# Booster_PA_OUT_HL.net
KiCad netlist of a schematic drawn in Altium Designer
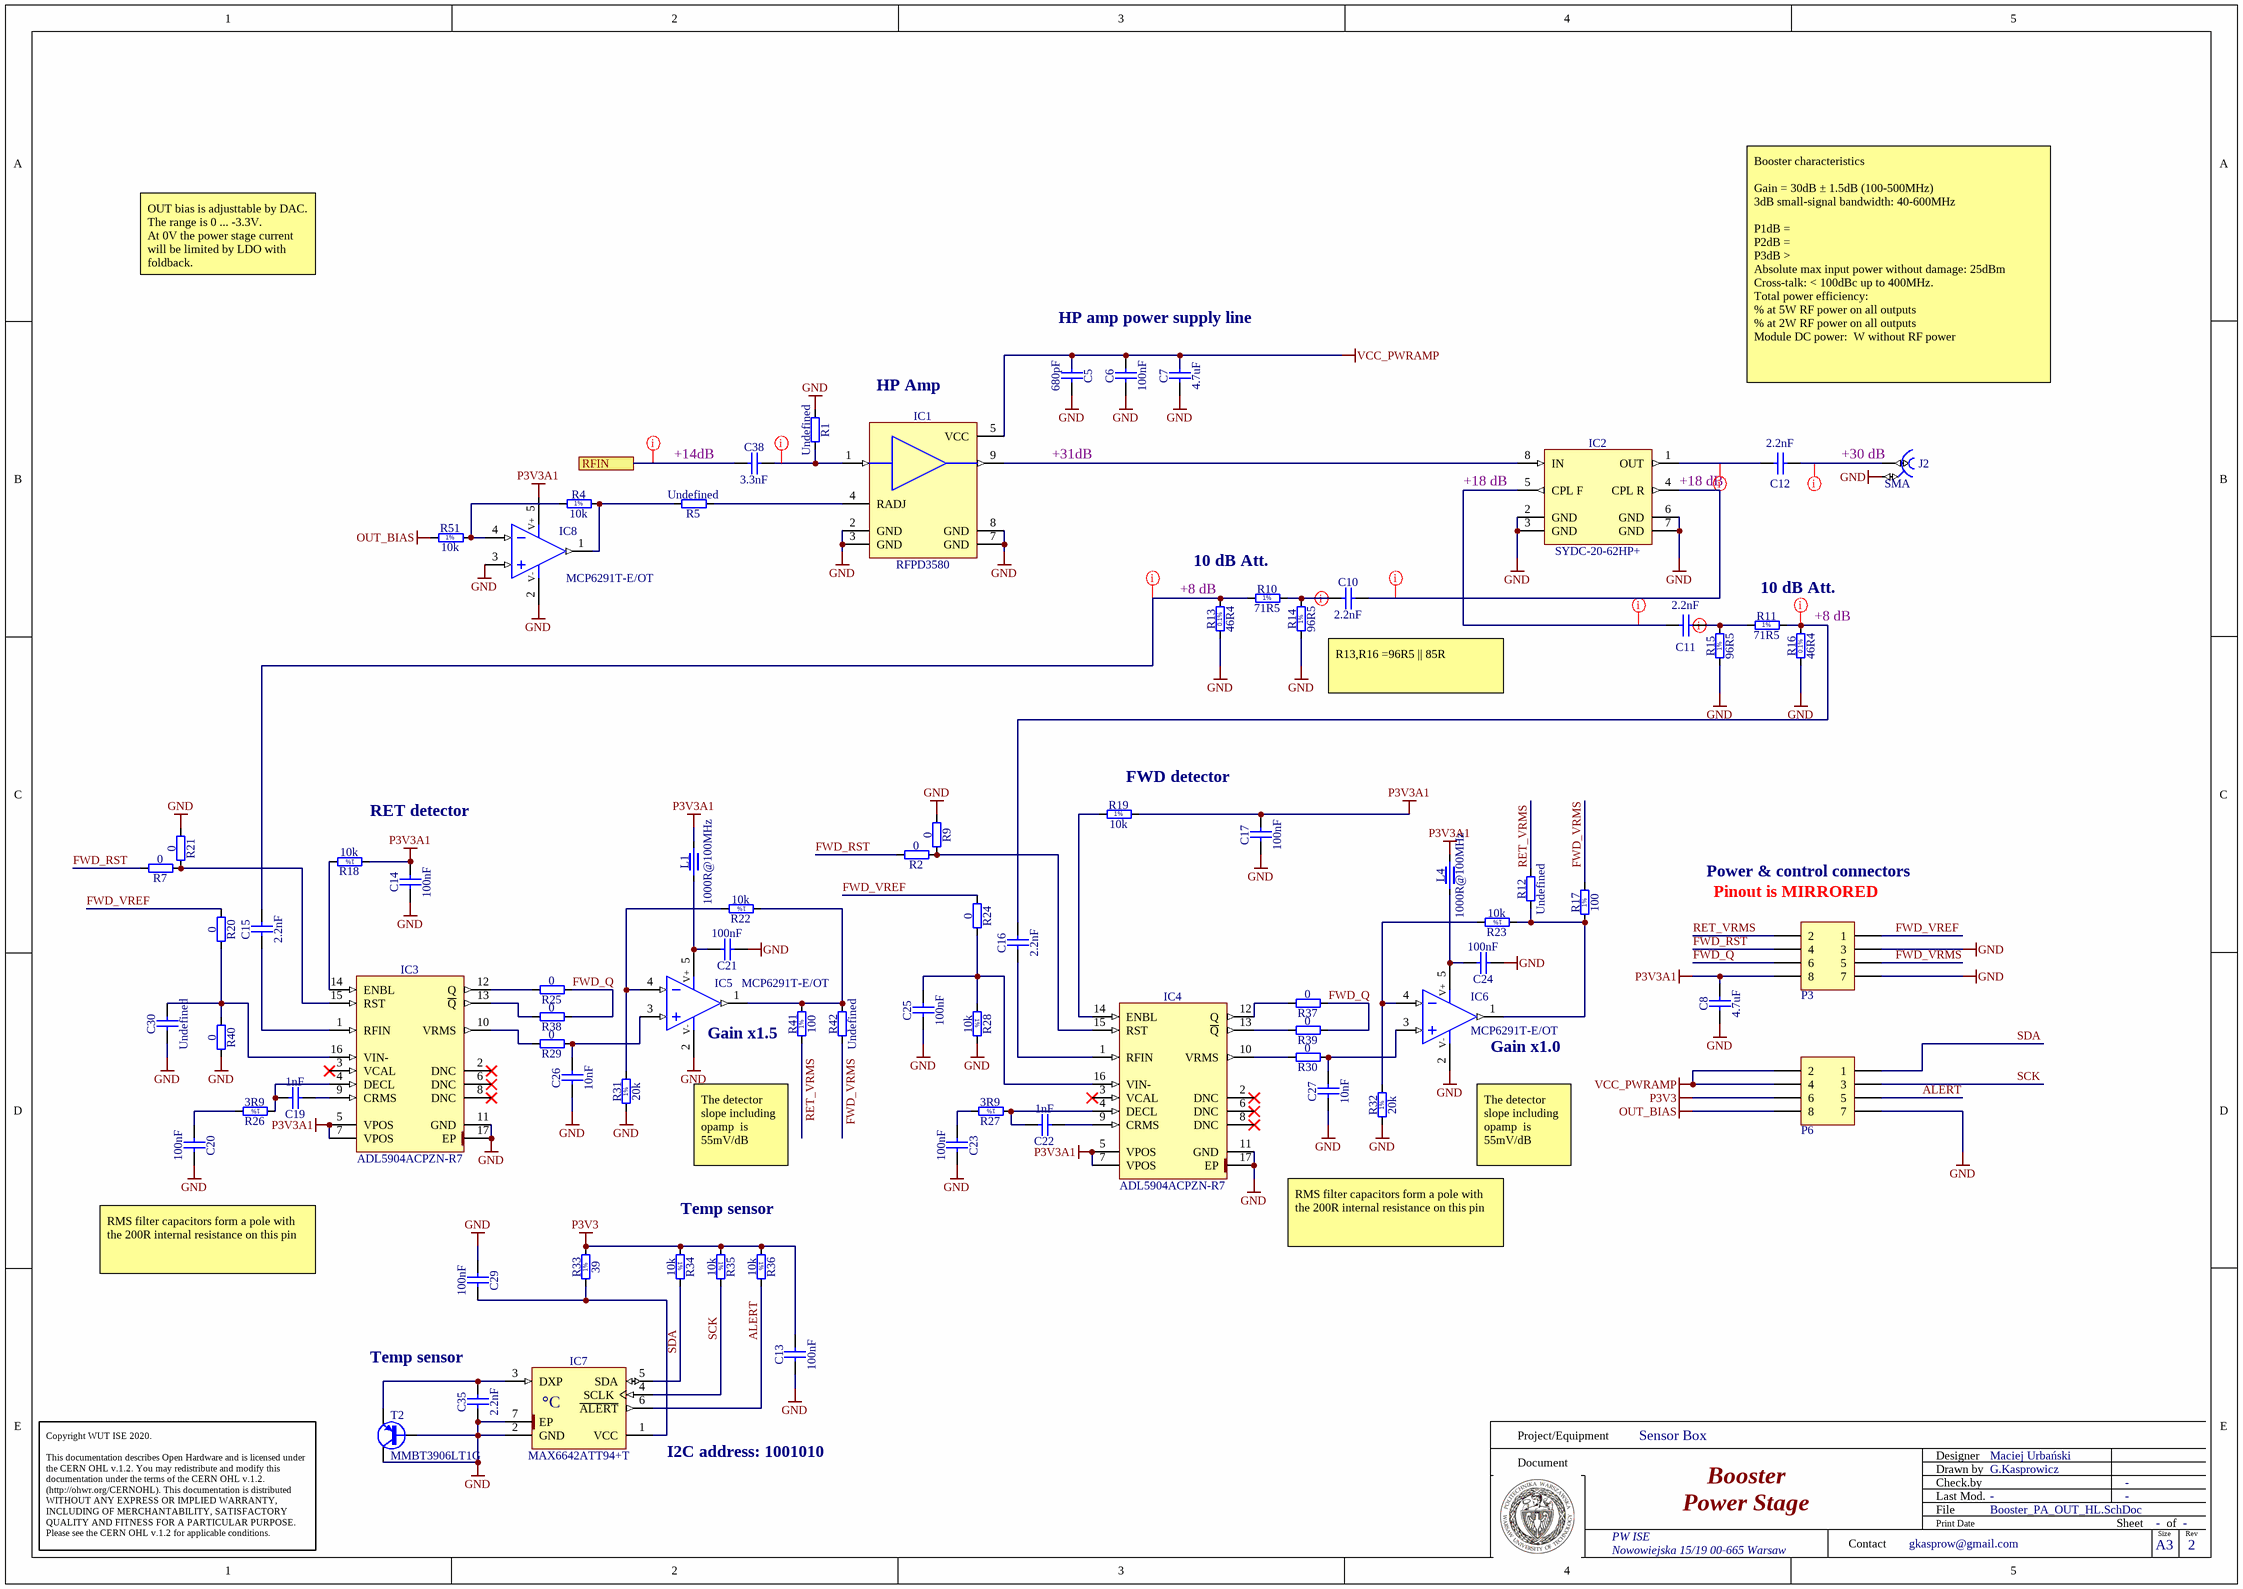
[diagram p0: Booster_PA_OUT_HL.SchDoc]

(export (version "E")
  (design (tool "Eeschema 10.0.6"))
  (components
    (comp (ref "C5")
      (value "680pF")
      (footprint "CAPC1608X87N")
      (description "Non-polarised capacitor")
      (fields
        (field (name "MANUFACTURER") "GENERIC")
        (field (name "MANUFACTURER PART NUMBER") "CC0603_680PF_50V_5%_NP0")
        (field (name "AUTHOR") "CERN DEM JLC")
      )
      (libsource (lib "Capacitors") (part "Capacitor - non polarized"))
    )
    (comp (ref "C6")
      (value "100nF")
      (footprint "CAPC1005X55N")
      (description "Non-polarised capacitor")
      (fields
        (field (name "MANUFACTURER") "GENERIC")
        (field (name "MANUFACTURER PART NUMBER") "CC0402_100NF_50V_10%_X7R")
        (field (name "AUTHOR") "CERN DEM MR")
      )
      (libsource (lib "Capacitors") (part "Capacitor - non polarized"))
    )
    (comp (ref "C7")
      (value "4.7uF")
      (footprint "CAPC3225X270N")
      (description "Non-polarised capacitor")
      (fields
        (field (name "PART NUMBER") "CC1210_4.7UF_50V_10%_X7R")
        (field (name "VOLTAGE") "50V")
        (field (name "AUTHOR") "CERN DEM JLC")
      )
      (libsource (lib "Capacitors") (part "Capacitor - non polarized"))
    )
    (comp (ref "C8")
      (value "4.7uF")
      (footprint "CAPC1709X95N")
      (description "Non-polarised capacitor")
      (fields
        (field (name "MANUFACTURER") "GENERIC")
        (field (name "MANUFACTURER PART NUMBER") "CC0603_4.7UF_16V_10%_X5R")
        (field (name "AUTHOR") "CERN DEM JLC")
      )
      (libsource (lib "Capacitors") (part "Capacitor - non polarized"))
    )
    (comp (ref "C10")
      (value "2.2nF")
      (footprint "CAPC1608X87N")
      (description "Non-polarised capacitor")
      (fields
        (field (name "PART NUMBER") "CC0603_2.2NF_50V_5%_C0G")
        (field (name "VOLTAGE") "50V")
        (field (name "AUTHOR") "CERN DEM JMW")
      )
      (libsource (lib "Capacitors") (part "Capacitor - non polarized"))
    )
    (comp (ref "C11")
      (value "2.2nF")
      (footprint "CAPC1608X87N")
      (description "Non-polarised capacitor")
      (fields
        (field (name "MANUFACTURER") "GENERIC")
        (field (name "MANUFACTURER PART NUMBER") "CC0603_2.2NF_50V_5%_C0G")
        (field (name "AUTHOR") "CERN DEM JMW")
      )
      (libsource (lib "Capacitors") (part "Capacitor - non polarized"))
    )
    (comp (ref "C12")
      (value "2.2nF")
      (footprint "CAPC1608X87N")
      (description "Non-polarised capacitor")
      (fields
        (field (name "MANUFACTURER") "GENERIC")
        (field (name "MANUFACTURER PART NUMBER") "CC0603_2.2NF_50V_5%_C0G")
        (field (name "AUTHOR") "CERN DEM JMW")
      )
      (libsource (lib "Capacitors") (part "Capacitor - non polarized"))
    )
    (comp (ref "C13")
      (value "100nF")
      (footprint "CAPC1005X55N")
      (description "Non-polarised capacitor")
      (fields
        (field (name "MANUFACTURER") "GENERIC")
        (field (name "MANUFACTURER PART NUMBER") "CC0402_100NF_50V_10%_X7R")
        (field (name "AUTHOR") "CERN DEM MR")
      )
      (libsource (lib "Capacitors") (part "Capacitor - non polarized"))
    )
    (comp (ref "C14")
      (value "100nF")
      (footprint "CAPC1005X55N")
      (description "Non-polarised capacitor")
      (fields
        (field (name "MANUFACTURER") "GENERIC")
        (field (name "MANUFACTURER PART NUMBER") "CC0402_100NF_50V_10%_X7R")
        (field (name "AUTHOR") "CERN DEM MR")
      )
      (libsource (lib "Capacitors") (part "Capacitor - non polarized"))
    )
    (comp (ref "C15")
      (value "2.2nF")
      (footprint "CAPC1608X87N")
      (description "Non-polarised capacitor")
      (fields
        (field (name "MANUFACTURER") "GENERIC")
        (field (name "MANUFACTURER PART NUMBER") "CC0603_2.2NF_50V_5%_C0G")
        (field (name "AUTHOR") "CERN DEM JMW")
      )
      (libsource (lib "Capacitors") (part "Capacitor - non polarized"))
    )
    (comp (ref "C16")
      (value "2.2nF")
      (footprint "CAPC1608X87N")
      (description "Non-polarised capacitor")
      (fields
        (field (name "MANUFACTURER") "GENERIC")
        (field (name "MANUFACTURER PART NUMBER") "CC0603_2.2NF_50V_5%_C0G")
        (field (name "AUTHOR") "CERN DEM JMW")
      )
      (libsource (lib "Capacitors") (part "Capacitor - non polarized"))
    )
    (comp (ref "C17")
      (value "100nF")
      (footprint "CAPC1005X55N")
      (description "Non-polarised capacitor")
      (fields
        (field (name "MANUFACTURER") "GENERIC")
        (field (name "MANUFACTURER PART NUMBER") "CC0402_100NF_50V_10%_X7R")
        (field (name "AUTHOR") "CERN DEM MR")
      )
      (libsource (lib "Capacitors") (part "Capacitor - non polarized"))
    )
    (comp (ref "C19")
      (value "1nF")
      (footprint "CAPC1005X55N")
      (description "Non-polarised capacitor")
      (fields
        (field (name "PART NUMBER") "CC0402_1NF_50V_10%_X7R")
        (field (name "VOLTAGE") "50V")
        (field (name "AUTHOR") "CERN DEM JLC")
      )
      (libsource (lib "Capacitors") (part "Capacitor - non polarized"))
    )
    (comp (ref "C20")
      (value "100nF")
      (footprint "CAPC1005X55N")
      (description "Non-polarised capacitor")
      (fields
        (field (name "MANUFACTURER") "GENERIC")
        (field (name "MANUFACTURER PART NUMBER") "CC0402_100NF_50V_10%_X7R")
        (field (name "AUTHOR") "CERN DEM MR")
      )
      (libsource (lib "Capacitors") (part "Capacitor - non polarized"))
    )
    (comp (ref "C21")
      (value "100nF")
      (footprint "CAPC1005X55N")
      (description "Non-polarised capacitor")
      (fields
        (field (name "MANUFACTURER") "GENERIC")
        (field (name "MANUFACTURER PART NUMBER") "CC0402_100NF_50V_10%_X7R")
        (field (name "AUTHOR") "CERN DEM MR")
      )
      (libsource (lib "Capacitors") (part "Capacitor - non polarized"))
    )
    (comp (ref "C22")
      (value "1nF")
      (footprint "CAPC1005X55N")
      (description "Non-polarised capacitor")
      (fields
        (field (name "PART NUMBER") "CC0402_1NF_50V_10%_X7R")
        (field (name "VOLTAGE") "50V")
        (field (name "AUTHOR") "CERN DEM JLC")
      )
      (libsource (lib "Capacitors") (part "Capacitor - non polarized"))
    )
    (comp (ref "C23")
      (value "100nF")
      (footprint "CAPC1005X55N")
      (description "Non-polarised capacitor")
      (fields
        (field (name "MANUFACTURER") "GENERIC")
        (field (name "MANUFACTURER PART NUMBER") "CC0402_100NF_50V_10%_X7R")
        (field (name "AUTHOR") "CERN DEM MR")
      )
      (libsource (lib "Capacitors") (part "Capacitor - non polarized"))
    )
    (comp (ref "C24")
      (value "100nF")
      (footprint "CAPC1005X55N")
      (description "Non-polarised capacitor")
      (fields
        (field (name "MANUFACTURER") "GENERIC")
        (field (name "MANUFACTURER PART NUMBER") "CC0402_100NF_50V_10%_X7R")
        (field (name "AUTHOR") "CERN DEM MR")
      )
      (libsource (lib "Capacitors") (part "Capacitor - non polarized"))
    )
    (comp (ref "C25")
      (value "100nF")
      (footprint "CAPC1005X55N")
      (description "Non-polarised capacitor")
      (fields
        (field (name "MANUFACTURER") "GENERIC")
        (field (name "MANUFACTURER PART NUMBER") "CC0402_100NF_50V_10%_X7R")
        (field (name "AUTHOR") "CERN DEM MR")
      )
      (libsource (lib "Capacitors") (part "Capacitor - non polarized"))
    )
    (comp (ref "C26")
      (value "10nF")
      (footprint "CAPC1005X55N")
      (description "Non-polarised capacitor")
      (fields
        (field (name "MANUFACTURER") "GENERIC")
        (field (name "MANUFACTURER PART NUMBER") "CC0402_10NF_25V_10%_X7R")
        (field (name "AUTHOR") "CERN DEM JLC")
      )
      (libsource (lib "Capacitors") (part "Capacitor - non polarized"))
    )
    (comp (ref "C27")
      (value "10nF")
      (footprint "CAPC1005X55N")
      (description "Non-polarised capacitor")
      (fields
        (field (name "MANUFACTURER") "GENERIC")
        (field (name "MANUFACTURER PART NUMBER") "CC0402_10NF_25V_10%_X7R")
        (field (name "AUTHOR") "CERN DEM JLC")
      )
      (libsource (lib "Capacitors") (part "Capacitor - non polarized"))
    )
    (comp (ref "C29")
      (value "100nF")
      (footprint "CAPC1005X55N")
      (description "Non-polarised capacitor")
      (fields
        (field (name "MANUFACTURER") "GENERIC")
        (field (name "MANUFACTURER PART NUMBER") "CC0402_100NF_50V_10%_X7R")
        (field (name "AUTHOR") "CERN DEM MR")
      )
      (libsource (lib "Capacitors") (part "Capacitor - non polarized"))
    )
    (comp (ref "C30")
      (value "Undefined")
      (footprint "CAPC1608X90N")
      (description "Non-polarised capacitor")
      (fields (field (name "PART NUMBER") "CC0603_NO-VALUE") (field (name "AUTHOR") "CERN DEM MR"))
      (libsource (lib "Capacitors") (part "Capacitor - non polarized"))
    )
    (comp (ref "C35")
      (value "2.2nF")
      (footprint "CAPC1608X87N")
      (description "Non-polarised capacitor")
      (fields
        (field (name "MANUFACTURER") "GENERIC")
        (field (name "MANUFACTURER PART NUMBER") "CC0603_2.2NF_50V_5%_C0G")
        (field (name "AUTHOR") "CERN DEM JMW")
      )
      (libsource (lib "Capacitors") (part "Capacitor - non polarized"))
    )
    (comp (ref "C38")
      (value "3.3nF")
      (footprint "CAPC1608X87N")
      (description "Non-polarised capacitor")
      (fields
        (field (name "MANUFACTURER") "GENERIC")
        (field (name "MANUFACTURER PART NUMBER") "CC0603_3.3NF_50V_5%_C0G")
        (field (name "AUTHOR") "CERN DEM MR")
      )
      (libsource (lib "Capacitors") (part "Capacitor - non polarized"))
    )
    (comp (ref "IC1")
      (value "RFPD3580")
      (footprint "SOT-115J_reversed")
      (description "GaAs/GaN Power Doubler Hybrid\r\n45MHz to 1218MHz")
      (fields (field (name "MANUFACTURER") "QORVO") (field (name "AUTHOR") "CERN DEM JLC"))
      (libsource (lib "ICs_Analog_Interfaces") (part "RF_RFPD3580"))
    )
    (comp (ref "IC2")
      (value "SYDC-20-62HP+")
      (footprint "MINI-CIRCUITS_AH202-1")
      (description "50Ohm, 10 to 540MHz, 25W, 20dB Bi-Directional Coupler")
      (fields (field (name "MANUFACTURER") "MINI-CIRCUITS") (field (name "AUTHOR") "CERN DEM BC"))
      (libsource (lib "ICs And Semiconductors") (part "SYDC-20-62HP+"))
    )
    (comp (ref "IC3")
      (value "ADL5904ACPZN-R7")
      (footprint "QFN50P300X300X80-17N-S175")
      (description "DC to 6 GHz, 45 dB TruPwr Detector With Envelope Threshold Detection")
      (fields (field (name "MANUFACTURER") "ANALOG DEVICES") (field (name "AUTHOR") "CERN DEM MR"))
      (libsource (lib "ICs And Semiconductors") (part "ADL5904"))
    )
    (comp (ref "IC4")
      (value "ADL5904ACPZN-R7")
      (footprint "QFN50P300X300X80-17N-S175")
      (description "DC to 6 GHz, 45 dB TruPwr Detector With Envelope Threshold Detection")
      (fields (field (name "MANUFACTURER") "ANALOG DEVICES") (field (name "AUTHOR") "CERN DEM MR"))
      (libsource (lib "ICs And Semiconductors") (part "ADL5904"))
    )
    (comp (ref "IC5")
      (value "MCP6291T-E/OT")
      (footprint "SOT95P270X145-5N")
      (description "Operational Amplifier")
      (fields (field (name "MANUFACTURER") "MICROCHIP TECHNOLOGY") (field (name "AUTHOR") "CERN DEM BC"))
      (libsource (lib "ICs And Semiconductors") (part "Operational Amplifier Type7"))
    )
    (comp (ref "IC6")
      (value "MCP6291T-E/OT")
      (footprint "SOT95P270X145-5N")
      (description "Operational Amplifier")
      (fields (field (name "MANUFACTURER") "MICROCHIP TECHNOLOGY") (field (name "AUTHOR") "CERN DEM BC"))
      (libsource (lib "ICs And Semiconductors") (part "Operational Amplifier Type7"))
    )
    (comp (ref "IC7")
      (value "MAX6642ATT94+T")
      (footprint "SON95P300X300X80-7N-R160X240")
      (description "±1°C, SMBus-Compatible Remote/Local Temperature Sensor with Overtemperature Alarm")
      (fields (field (name "MANUFACTURER") "MAXIM") (field (name "AUTHOR") "CERN DEM JLC"))
      (libsource (lib "ICs And Semiconductors") (part "MAX6642ATT"))
    )
    (comp (ref "IC8")
      (value "MCP6291T-E/OT")
      (footprint "SOT95P270X145-5N")
      (description "Operational Amplifier")
      (fields (field (name "MANUFACTURER") "MICROCHIP TECHNOLOGY") (field (name "AUTHOR") "CERN DEM BC"))
      (libsource (lib "ICs And Semiconductors") (part "Operational Amplifier Type7"))
    )
    (comp (ref "J2")
      (value "SMA")
      (footprint "MOLEX_73251-2120")
      (description "50 Ohm, SMA Edge Mount PCB, With Jam Nut And Lock Washer")
      (fields
        (field (name "PART NUMBER") "MOLEX_73251-2120")
        (field (name "MANUFACTURER") "MOLEX")
        (field (name "AUTHOR") "CERN DEM JLC")
      )
      (libsource (lib "Connectors") (part "CON_SMA_RA_SMD_73251-2120"))
    )
    (comp (ref "L1")
      (value "1000R@100MHz")
      (footprint "INDC1608X95N")
      (fields
        (field (name "MANUFACTURER") "MURATA")
        (field (name "MANUFACTURER PART NUMBER") "BLM18HE102SN1")
        (field (name "PART NUMBER") "IND0603_MURATA_BLM18HE102SN1")
        (field (name "AUTHOR") "CERN DEM JLC")
      )
      (libsource (lib "Inductors & Transformers") (part "Ferrite Bead"))
    )
    (comp (ref "L4")
      (value "1000R@100MHz")
      (footprint "INDC1608X95N")
      (fields
        (field (name "MANUFACTURER") "MURATA")
        (field (name "MANUFACTURER PART NUMBER") "BLM18HE102SN1")
        (field (name "PART NUMBER") "IND0603_MURATA_BLM18HE102SN1")
        (field (name "AUTHOR") "CERN DEM JLC")
      )
      (libsource (lib "Inductors & Transformers") (part "Ferrite Bead"))
    )
    (comp (ref "P3")
      (value "ZL264-8DG")
      (footprint "HDR2X4_SMD")
      (description "Header, 4-Pin, Dual Row")
      (libsource (lib "onyks") (part "HDR2X4"))
    )
    (comp (ref "P6")
      (value "ZL264-8DG")
      (footprint "HDR2X4_SMD")
      (description "Header, 4-Pin, Dual Row")
      (libsource (lib "onyks") (part "HDR2X4"))
    )
    (comp (ref "R1")
      (value "Undefined")
      (footprint "RESC1608X55N")
      (description "Resistor")
      (fields
        (field (name "MANUFACTURER PART NUMBER") "R0603_NO-VALUE")
        (field (name "AUTHOR") "CERN DEM JLC")
      )
      (libsource (lib "Resistors") (part "Resistor"))
    )
    (comp (ref "R2")
      (value "0")
      (footprint "RESC1005X40N")
      (description "Resistor")
      (fields
        (field (name "MANUFACTURER") "GENERIC")
        (field (name "MANUFACTURER PART NUMBER") "R0402_0R_JUMPER")
        (field (name "AUTHOR") "CERN DEM JLC")
      )
      (libsource (lib "Resistors") (part "Resistor"))
    )
    (comp (ref "R4")
      (value "10k")
      (footprint "RESC1005X40N")
      (description "Resistor - 1%")
      (fields
        (field (name "MANUFACTURER") "GENERIC")
        (field (name "MANUFACTURER PART NUMBER") "R0402_10K_1%_0.0625W_100PPM")
        (field (name "AUTHOR") "CERN DEM JLC")
      )
      (libsource (lib "Resistors") (part "Resistor - 1%"))
    )
    (comp (ref "R5")
      (value "Undefined")
      (footprint "RESC1608X55N")
      (description "Resistor")
      (fields
        (field (name "MANUFACTURER PART NUMBER") "R0603_NO-VALUE")
        (field (name "AUTHOR") "CERN DEM JLC")
      )
      (libsource (lib "Resistors") (part "Resistor"))
    )
    (comp (ref "R7")
      (value "0")
      (footprint "RESC1005X40N")
      (description "Resistor")
      (fields
        (field (name "MANUFACTURER") "GENERIC")
        (field (name "MANUFACTURER PART NUMBER") "R0402_0R_JUMPER")
        (field (name "AUTHOR") "CERN DEM JLC")
      )
      (libsource (lib "Resistors") (part "Resistor"))
    )
    (comp (ref "R9")
      (value "0")
      (footprint "RESC1005X40N")
      (description "Resistor")
      (fields
        (field (name "MANUFACTURER") "GENERIC")
        (field (name "MANUFACTURER PART NUMBER") "R0402_0R_JUMPER")
        (field (name "AUTHOR") "CERN DEM JLC")
      )
      (libsource (lib "Resistors") (part "Resistor"))
    )
    (comp (ref "R10")
      (value "71R5")
      (footprint "RESC1608X55N")
      (description "Resistor - 1%")
      (fields
        (field (name "PART NUMBER") "R0603_71R5_1%_0.1W_100PPM")
        (field (name "POWER") "0.1W")
        (field (name "AUTHOR") "CERN DEM JLC")
      )
      (libsource (lib "Resistors") (part "Resistor - 1%"))
    )
    (comp (ref "R11")
      (value "71R5")
      (footprint "RESC1608X55N")
      (description "Resistor - 1%")
      (fields
        (field (name "PART NUMBER") "R0603_71R5_1%_0.1W_100PPM")
        (field (name "POWER") "0.1W")
        (field (name "AUTHOR") "CERN DEM JLC")
      )
      (libsource (lib "Resistors") (part "Resistor - 1%"))
    )
    (comp (ref "R12")
      (value "Undefined")
      (footprint "RESC1608X55N")
      (description "Resistor")
      (fields
        (field (name "MANUFACTURER PART NUMBER") "R0603_NO-VALUE")
        (field (name "AUTHOR") "CERN DEM JLC")
      )
      (libsource (lib "Resistors") (part "Resistor"))
    )
    (comp (ref "R13")
      (value "46R4")
      (footprint "RESC1608X55N")
      (description "Resistor - 0.1%")
      (fields
        (field (name "PART NUMBER") "R0603_46R4_0.1%_0.063W_10PPM")
        (field (name "POWER") "0.063W")
        (field (name "AUTHOR") "CERN DEM JLC")
      )
      (libsource (lib "Resistors") (part "Resistor - 0.1%"))
    )
    (comp (ref "R14")
      (value "96R5")
      (footprint "RESC1608X55N")
      (description "Resistor - 0.5%")
      (fields
        (field (name "PART NUMBER") "R0603_96R5_0.5%_0.1W_50PPM")
        (field (name "POWER") "0.1W")
        (field (name "AUTHOR") "GK")
      )
      (libsource (lib "Passives_RC") (part "R0603_96R5_0.5%_0.1W_50PPM"))
    )
    (comp (ref "R15")
      (value "96R5")
      (footprint "RESC1608X55N")
      (description "Resistor - 0.5%")
      (fields
        (field (name "PART NUMBER") "R0603_96R5_0.5%_0.1W_50PPM")
        (field (name "POWER") "0.1W")
        (field (name "AUTHOR") "GK")
      )
      (libsource (lib "Passives_RC") (part "R0603_96R5_0.5%_0.1W_50PPM"))
    )
    (comp (ref "R16")
      (value "46R4")
      (footprint "RESC1608X55N")
      (description "Resistor - 0.1%")
      (fields
        (field (name "PART NUMBER") "R0603_46R4_0.1%_0.063W_10PPM")
        (field (name "POWER") "0.063W")
        (field (name "AUTHOR") "CERN DEM JLC")
      )
      (libsource (lib "Resistors") (part "Resistor - 0.1%"))
    )
    (comp (ref "R17")
      (value "100")
      (footprint "RESC1608X55N")
      (description "Resistor - 1%")
      (fields
        (field (name "MANUFACTURER") "GENERIC")
        (field (name "MANUFACTURER PART NUMBER") "R0603_100R_1%_0.1W_100PPM")
        (field (name "AUTHOR") "CERN DEM JLC")
      )
      (libsource (lib "Resistors") (part "Resistor - 1%"))
    )
    (comp (ref "R18")
      (value "10k")
      (footprint "RESC1005X40N")
      (description "Resistor - 1%")
      (fields
        (field (name "MANUFACTURER") "GENERIC")
        (field (name "MANUFACTURER PART NUMBER") "R0402_10K_1%_0.0625W_100PPM")
        (field (name "AUTHOR") "CERN DEM JLC")
      )
      (libsource (lib "Resistors") (part "Resistor - 1%"))
    )
    (comp (ref "R19")
      (value "10k")
      (footprint "RESC1005X40N")
      (description "Resistor - 1%")
      (fields
        (field (name "PART NUMBER") "R0402_10K_1%_0.0625W_100PPM")
        (field (name "POWER") "0.0625W")
        (field (name "AUTHOR") "CERN DEM JLC")
      )
      (libsource (lib "Resistors") (part "Resistor - 1%"))
    )
    (comp (ref "R20")
      (value "0")
      (footprint "RESC1005X40N")
      (description "Resistor")
      (fields
        (field (name "MANUFACTURER") "GENERIC")
        (field (name "MANUFACTURER PART NUMBER") "R0402_0R_JUMPER")
        (field (name "AUTHOR") "CERN DEM JLC")
      )
      (libsource (lib "Resistors") (part "Resistor"))
    )
    (comp (ref "R21")
      (value "0")
      (footprint "RESC1005X40N")
      (description "Resistor")
      (fields
        (field (name "MANUFACTURER") "GENERIC")
        (field (name "MANUFACTURER PART NUMBER") "R0402_0R_JUMPER")
        (field (name "AUTHOR") "CERN DEM JLC")
      )
      (libsource (lib "Resistors") (part "Resistor"))
    )
    (comp (ref "R22")
      (value "10k")
      (footprint "RESC1005X40N")
      (description "Resistor - 1%")
      (fields
        (field (name "MANUFACTURER") "GENERIC")
        (field (name "MANUFACTURER PART NUMBER") "R0402_10K_1%_0.0625W_100PPM")
        (field (name "AUTHOR") "CERN DEM JLC")
      )
      (libsource (lib "Resistors") (part "Resistor - 1%"))
    )
    (comp (ref "R23")
      (value "10k")
      (footprint "RESC1005X40N")
      (description "Resistor - 1%")
      (fields
        (field (name "MANUFACTURER") "GENERIC")
        (field (name "MANUFACTURER PART NUMBER") "R0402_10K_1%_0.0625W_100PPM")
        (field (name "AUTHOR") "CERN DEM JLC")
      )
      (libsource (lib "Resistors") (part "Resistor - 1%"))
    )
    (comp (ref "R24")
      (value "0")
      (footprint "RESC1005X40N")
      (description "Resistor")
      (fields
        (field (name "MANUFACTURER") "GENERIC")
        (field (name "MANUFACTURER PART NUMBER") "R0402_0R_JUMPER")
        (field (name "AUTHOR") "CERN DEM JLC")
      )
      (libsource (lib "Resistors") (part "Resistor"))
    )
    (comp (ref "R25")
      (value "0")
      (footprint "RESC1005X40N")
      (description "Resistor")
      (fields
        (field (name "MANUFACTURER") "GENERIC")
        (field (name "MANUFACTURER PART NUMBER") "R0402_0R_JUMPER")
        (field (name "AUTHOR") "CERN DEM JLC")
      )
      (libsource (lib "Resistors") (part "Resistor"))
    )
    (comp (ref "R26")
      (value "3R9")
      (footprint "RESC1005X40N")
      (description "Resistor - 1%")
      (fields
        (field (name "PART NUMBER") "R0402_3R9_1%_0.0625W_200PPM")
        (field (name "POWER") "0.0625W")
        (field (name "AUTHOR") "CERN DEM JLC")
      )
      (libsource (lib "Resistors") (part "Resistor - 1%"))
    )
    (comp (ref "R27")
      (value "3R9")
      (footprint "RESC1005X40N")
      (description "Resistor - 1%")
      (fields
        (field (name "PART NUMBER") "R0402_3R9_1%_0.0625W_200PPM")
        (field (name "POWER") "0.0625W")
        (field (name "AUTHOR") "CERN DEM JLC")
      )
      (libsource (lib "Resistors") (part "Resistor - 1%"))
    )
    (comp (ref "R28")
      (value "10k")
      (footprint "RESC1005X40N")
      (description "Resistor - 1%")
      (fields
        (field (name "MANUFACTURER") "GENERIC")
        (field (name "MANUFACTURER PART NUMBER") "R0402_10K_1%_0.0625W_100PPM")
        (field (name "AUTHOR") "CERN DEM JLC")
      )
      (libsource (lib "Resistors") (part "Resistor - 1%"))
    )
    (comp (ref "R29")
      (value "0")
      (footprint "RESC1005X40N")
      (description "Resistor")
      (fields
        (field (name "MANUFACTURER") "GENERIC")
        (field (name "MANUFACTURER PART NUMBER") "R0402_0R_JUMPER")
        (field (name "AUTHOR") "CERN DEM JLC")
      )
      (libsource (lib "Resistors") (part "Resistor"))
    )
    (comp (ref "R30")
      (value "0")
      (footprint "RESC1005X40N")
      (description "Resistor")
      (fields
        (field (name "MANUFACTURER") "GENERIC")
        (field (name "MANUFACTURER PART NUMBER") "R0402_0R_JUMPER")
        (field (name "AUTHOR") "CERN DEM JLC")
      )
      (libsource (lib "Resistors") (part "Resistor"))
    )
    (comp (ref "R31")
      (value "20k")
      (footprint "RESC1608X55N")
      (description "Resistor - 1%")
      (fields
        (field (name "PART NUMBER") "R0603_20K_1%_0.1W_100PPM")
        (field (name "POWER") "0.1W")
        (field (name "AUTHOR") "CERN DEM JLC")
      )
      (libsource (lib "Resistors") (part "Resistor - 1%"))
    )
    (comp (ref "R32")
      (value "20k")
      (footprint "RESC1608X55N")
      (description "Resistor - 1%")
      (fields
        (field (name "PART NUMBER") "R0603_20K_1%_0.1W_100PPM")
        (field (name "POWER") "0.1W")
        (field (name "AUTHOR") "CERN DEM JLC")
      )
      (libsource (lib "Resistors") (part "Resistor - 1%"))
    )
    (comp (ref "R33")
      (value "39")
      (footprint "RESC1608X55N")
      (description "Resistor - 1%")
      (fields
        (field (name "PART NUMBER") "R0603_39R_1%_0.1W_100PPM")
        (field (name "POWER") "0.1W")
        (field (name "AUTHOR") "CERN DEM JLC")
      )
      (libsource (lib "Resistors") (part "Resistor - 1%"))
    )
    (comp (ref "R34")
      (value "10k")
      (footprint "RESC1005X40N")
      (description "Resistor - 1%")
      (fields
        (field (name "MANUFACTURER") "GENERIC")
        (field (name "MANUFACTURER PART NUMBER") "R0402_10K_1%_0.0625W_100PPM")
        (field (name "AUTHOR") "CERN DEM JLC")
      )
      (libsource (lib "Resistors") (part "Resistor - 1%"))
    )
    (comp (ref "R35")
      (value "10k")
      (footprint "RESC1005X40N")
      (description "Resistor - 1%")
      (fields
        (field (name "MANUFACTURER") "GENERIC")
        (field (name "MANUFACTURER PART NUMBER") "R0402_10K_1%_0.0625W_100PPM")
        (field (name "AUTHOR") "CERN DEM JLC")
      )
      (libsource (lib "Resistors") (part "Resistor - 1%"))
    )
    (comp (ref "R36")
      (value "10k")
      (footprint "RESC1005X40N")
      (description "Resistor - 1%")
      (fields
        (field (name "MANUFACTURER") "GENERIC")
        (field (name "MANUFACTURER PART NUMBER") "R0402_10K_1%_0.0625W_100PPM")
        (field (name "AUTHOR") "CERN DEM JLC")
      )
      (libsource (lib "Resistors") (part "Resistor - 1%"))
    )
    (comp (ref "R37")
      (value "0")
      (footprint "RESC1005X40N")
      (description "Resistor")
      (fields
        (field (name "MANUFACTURER") "GENERIC")
        (field (name "MANUFACTURER PART NUMBER") "R0402_0R_JUMPER")
        (field (name "AUTHOR") "CERN DEM JLC")
      )
      (libsource (lib "Resistors") (part "Resistor"))
    )
    (comp (ref "R38")
      (value "0")
      (footprint "RESC1005X40N")
      (description "Resistor")
      (fields
        (field (name "MANUFACTURER") "GENERIC")
        (field (name "MANUFACTURER PART NUMBER") "R0402_0R_JUMPER")
        (field (name "AUTHOR") "CERN DEM JLC")
      )
      (libsource (lib "Resistors") (part "Resistor"))
    )
    (comp (ref "R39")
      (value "0")
      (footprint "RESC1005X40N")
      (description "Resistor")
      (fields
        (field (name "MANUFACTURER") "GENERIC")
        (field (name "MANUFACTURER PART NUMBER") "R0402_0R_JUMPER")
        (field (name "AUTHOR") "CERN DEM JLC")
      )
      (libsource (lib "Resistors") (part "Resistor"))
    )
    (comp (ref "R40")
      (value "0")
      (footprint "RESC1005X40N")
      (description "Resistor")
      (fields
        (field (name "MANUFACTURER") "GENERIC")
        (field (name "MANUFACTURER PART NUMBER") "R0402_0R_JUMPER")
        (field (name "AUTHOR") "CERN DEM JLC")
      )
      (libsource (lib "Resistors") (part "Resistor"))
    )
    (comp (ref "R41")
      (value "100")
      (footprint "RESC1608X55N")
      (description "Resistor - 1%")
      (fields
        (field (name "MANUFACTURER") "GENERIC")
        (field (name "MANUFACTURER PART NUMBER") "R0603_100R_1%_0.1W_100PPM")
        (field (name "AUTHOR") "CERN DEM JLC")
      )
      (libsource (lib "Resistors") (part "Resistor - 1%"))
    )
    (comp (ref "R42")
      (value "Undefined")
      (footprint "RESC1608X55N")
      (description "Resistor")
      (fields
        (field (name "MANUFACTURER PART NUMBER") "R0603_NO-VALUE")
        (field (name "AUTHOR") "CERN DEM JLC")
      )
      (libsource (lib "Resistors") (part "Resistor"))
    )
    (comp (ref "R51")
      (value "10k")
      (footprint "RESC1005X40N")
      (description "Resistor - 1%")
      (fields
        (field (name "MANUFACTURER") "GENERIC")
        (field (name "MANUFACTURER PART NUMBER") "R0402_10K_1%_0.0625W_100PPM")
        (field (name "AUTHOR") "CERN DEM JLC")
      )
      (libsource (lib "Resistors") (part "Resistor - 1%"))
    )
    (comp (ref "T2")
      (value "MMBT3906LT1G")
      (footprint "SOT95P240X110-3N")
      (description "PNP Transistor")
      (fields (field (name "MANUFACTURER") "ON SEMICONDUCTOR") (field (name "AUTHOR") "CERN DEM JLC"))
      (libsource (lib "ICs And Semiconductors") (part "PNP B1 E2 C3"))
    )
  )
  (nets
    (net (code "1") (name "/ALERT") (class "Default")
      (node (ref "IC7") (pin "6") (pinfunction "~{ALERT}_6") (pintype "output"))
      (node (ref "P6") (pin "5") (pinfunction "5_5") (pintype "passive"))
      (node (ref "R36") (pin "2") (pinfunction "2_2") (pintype "passive"))
    )
    (net (code "2") (name "/FWD_Q") (class "Default")
      (node (ref "P3") (pin "6") (pinfunction "6_6") (pintype "passive"))
      (node (ref "R25") (pin "1") (pinfunction "1_1") (pintype "passive"))
      (node (ref "R37") (pin "1") (pinfunction "1_1") (pintype "passive"))
      (node (ref "R38") (pin "1") (pinfunction "1_1") (pintype "passive"))
      (node (ref "R39") (pin "1") (pinfunction "1_1") (pintype "passive"))
    )
    (net (code "3") (name "/FWD_RST") (class "Default")
      (node (ref "P3") (pin "4") (pinfunction "4_4") (pintype "passive"))
      (node (ref "R2") (pin "2") (pinfunction "2_2") (pintype "passive"))
      (node (ref "R7") (pin "2") (pinfunction "2_2") (pintype "passive"))
    )
    (net (code "4") (name "/FWD_VREF") (class "Default")
      (node (ref "P3") (pin "1") (pinfunction "1_1") (pintype "passive"))
      (node (ref "R20") (pin "1") (pinfunction "1_1") (pintype "passive"))
      (node (ref "R24") (pin "1") (pinfunction "1_1") (pintype "passive"))
    )
    (net (code "5") (name "/FWD_VRMS") (class "Default")
      (node (ref "P3") (pin "5") (pinfunction "5_5") (pintype "passive"))
      (node (ref "R17") (pin "2") (pinfunction "2_2") (pintype "passive"))
      (node (ref "R42") (pin "1") (pinfunction "1_1") (pintype "passive"))
    )
    (net (code "6") (name "/RET_VRMS") (class "Default")
      (node (ref "P3") (pin "2") (pinfunction "2_2") (pintype "passive"))
      (node (ref "R12") (pin "2") (pinfunction "2_2") (pintype "passive"))
      (node (ref "R41") (pin "1") (pinfunction "1_1") (pintype "passive"))
    )
    (net (code "7") (name "/RFIN") (class "Default")
      (node (ref "C38") (pin "2") (pinfunction "2_2") (pintype "passive"))
    )
    (net (code "8") (name "/SCK") (class "Default")
      (node (ref "IC7") (pin "4") (pinfunction "SCLK_4") (pintype "input"))
      (node (ref "P6") (pin "3") (pinfunction "3_3") (pintype "passive"))
      (node (ref "R35") (pin "2") (pinfunction "2_2") (pintype "passive"))
    )
    (net (code "9") (name "/SDA") (class "Default")
      (node (ref "IC7") (pin "5") (pinfunction "SDA_5") (pintype "bidirectional"))
      (node (ref "P6") (pin "1") (pinfunction "1_1") (pintype "passive"))
      (node (ref "R34") (pin "2") (pinfunction "2_2") (pintype "passive"))
    )
    (net (code "10") (name "GND") (class "Default")
      (node (ref "C13") (pin "1") (pinfunction "1_1") (pintype "passive"))
      (node (ref "C14") (pin "1") (pinfunction "1_1") (pintype "passive"))
      (node (ref "C17") (pin "1") (pinfunction "1_1") (pintype "passive"))
      (node (ref "C20") (pin "2") (pinfunction "2_2") (pintype "passive"))
      (node (ref "C21") (pin "1") (pinfunction "1_1") (pintype "passive"))
      (node (ref "C23") (pin "2") (pinfunction "2_2") (pintype "passive"))
      (node (ref "C24") (pin "1") (pinfunction "1_1") (pintype "passive"))
      (node (ref "C25") (pin "1") (pinfunction "1_1") (pintype "passive"))
      (node (ref "C26") (pin "1") (pinfunction "1_1") (pintype "passive"))
      (node (ref "C27") (pin "1") (pinfunction "1_1") (pintype "passive"))
      (node (ref "C29") (pin "1") (pinfunction "1_1") (pintype "passive"))
      (node (ref "C30") (pin "1") (pinfunction "1_1") (pintype "passive"))
      (node (ref "C35") (pin "1") (pinfunction "1_1") (pintype "passive"))
      (node (ref "C5") (pin "1") (pinfunction "1_1") (pintype "passive"))
      (node (ref "C6") (pin "1") (pinfunction "1_1") (pintype "passive"))
      (node (ref "C7") (pin "1") (pinfunction "1_1") (pintype "passive"))
      (node (ref "C8") (pin "1") (pinfunction "1_1") (pintype "passive"))
      (node (ref "IC1") (pin "2") (pinfunction "GND_2") (pintype "power_in"))
      (node (ref "IC1") (pin "3") (pinfunction "GND_3") (pintype "power_in"))
      (node (ref "IC1") (pin "7") (pinfunction "GND_7") (pintype "power_in"))
      (node (ref "IC1") (pin "8") (pinfunction "GND_8") (pintype "power_in"))
      (node (ref "IC2") (pin "2") (pinfunction "GND_2") (pintype "power_in"))
      (node (ref "IC2") (pin "3") (pinfunction "GND_3") (pintype "power_in"))
      (node (ref "IC2") (pin "6") (pinfunction "GND_6") (pintype "power_in"))
      (node (ref "IC2") (pin "7") (pinfunction "GND_7") (pintype "power_in"))
      (node (ref "IC3") (pin "11") (pinfunction "GND_11") (pintype "power_in"))
      (node (ref "IC3") (pin "17") (pinfunction "EP_17") (pintype "power_in"))
      (node (ref "IC4") (pin "11") (pinfunction "GND_11") (pintype "power_in"))
      (node (ref "IC4") (pin "17") (pinfunction "EP_17") (pintype "power_in"))
      (node (ref "IC5") (pin "2") (pinfunction "V-_2") (pintype "power_in"))
      (node (ref "IC6") (pin "2") (pinfunction "V-_2") (pintype "power_in"))
      (node (ref "IC7") (pin "2") (pinfunction "GND_2") (pintype "power_in"))
      (node (ref "IC7") (pin "7") (pinfunction "EP_7") (pintype "power_in"))
      (node (ref "IC8") (pin "2") (pinfunction "V-_2") (pintype "power_in"))
      (node (ref "IC8") (pin "3") (pinfunction "IN+_3") (pintype "input"))
      (node (ref "J2") (pin "2") (pinfunction "2_2") (pintype "bidirectional"))
      (node (ref "P3") (pin "3") (pinfunction "3_3") (pintype "passive"))
      (node (ref "P3") (pin "7") (pinfunction "7_7") (pintype "passive"))
      (node (ref "P6") (pin "7") (pinfunction "7_7") (pintype "passive"))
      (node (ref "R1") (pin "1") (pinfunction "1_1") (pintype "passive"))
      (node (ref "R13") (pin "1") (pinfunction "1_1") (pintype "passive"))
      (node (ref "R14") (pin "1") (pinfunction "1_1") (pintype "passive"))
      (node (ref "R15") (pin "1") (pinfunction "1_1") (pintype "passive"))
      (node (ref "R16") (pin "1") (pinfunction "1_1") (pintype "passive"))
      (node (ref "R21") (pin "1") (pinfunction "1_1") (pintype "passive"))
      (node (ref "R28") (pin "2") (pinfunction "2_2") (pintype "passive"))
      (node (ref "R31") (pin "1") (pinfunction "1_1") (pintype "passive"))
      (node (ref "R32") (pin "1") (pinfunction "1_1") (pintype "passive"))
      (node (ref "R40") (pin "2") (pinfunction "2_2") (pintype "passive"))
      (node (ref "R9") (pin "1") (pinfunction "1_1") (pintype "passive"))
      (node (ref "T2") (pin "1") (pinfunction "B_1") (pintype "passive"))
      (node (ref "T2") (pin "3") (pinfunction "C_3") (pintype "passive"))
    )
    (net (code "11") (name "Net-(C10-Pad1)") (class "Default")
      (node (ref "C10") (pin "1") (pinfunction "1_1") (pintype "passive"))
      (node (ref "R10") (pin "2") (pinfunction "2_2") (pintype "passive"))
      (node (ref "R14") (pin "2") (pinfunction "2_2") (pintype "passive"))
    )
    (net (code "12") (name "Net-(C11-Pad1)") (class "Default")
      (node (ref "C11") (pin "1") (pinfunction "1_1") (pintype "passive"))
      (node (ref "R11") (pin "1") (pinfunction "1_1") (pintype "passive"))
      (node (ref "R15") (pin "2") (pinfunction "2_2") (pintype "passive"))
    )
    (net (code "13") (name "Net-(C12-Pad1)") (class "Default")
      (node (ref "C12") (pin "1") (pinfunction "1_1") (pintype "passive"))
      (node (ref "J2") (pin "1") (pinfunction "1_1") (pintype "bidirectional"))
    )
    (net (code "14") (name "Net-(C15-Pad2)") (class "Default")
      (node (ref "C15") (pin "2") (pinfunction "2_2") (pintype "passive"))
      (node (ref "R10") (pin "1") (pinfunction "1_1") (pintype "passive"))
      (node (ref "R13") (pin "2") (pinfunction "2_2") (pintype "passive"))
    )
    (net (code "15") (name "Net-(C16-Pad2)") (class "Default")
      (node (ref "C16") (pin "2") (pinfunction "2_2") (pintype "passive"))
      (node (ref "R11") (pin "2") (pinfunction "2_2") (pintype "passive"))
      (node (ref "R16") (pin "2") (pinfunction "2_2") (pintype "passive"))
    )
    (net (code "16") (name "Net-(C20-Pad1)") (class "Default")
      (node (ref "C20") (pin "1") (pinfunction "1_1") (pintype "passive"))
      (node (ref "R26") (pin "2") (pinfunction "2_2") (pintype "passive"))
    )
    (net (code "17") (name "Net-(C23-Pad1)") (class "Default")
      (node (ref "C23") (pin "1") (pinfunction "1_1") (pintype "passive"))
      (node (ref "R27") (pin "2") (pinfunction "2_2") (pintype "passive"))
    )
    (net (code "18") (name "Net-(IC1-RADJ)") (class "Default")
      (node (ref "IC1") (pin "4") (pinfunction "RADJ_4") (pintype "passive"))
      (node (ref "R5") (pin "1") (pinfunction "1_1") (pintype "passive"))
    )
    (net (code "19") (name "Net-(IC1-RF_IN)") (class "Default")
      (node (ref "C38") (pin "1") (pinfunction "1_1") (pintype "passive"))
      (node (ref "IC1") (pin "1") (pinfunction "RF_IN_1") (pintype "input"))
      (node (ref "R1") (pin "2") (pinfunction "2_2") (pintype "passive"))
    )
    (net (code "20") (name "Net-(IC1-RF_OUT)") (class "Default")
      (node (ref "IC1") (pin "9") (pinfunction "RF_OUT_9") (pintype "output"))
      (node (ref "IC2") (pin "8") (pinfunction "IN_8") (pintype "input"))
    )
    (net (code "21") (name "Net-(IC2-CPL_F)") (class "Default")
      (node (ref "C11") (pin "2") (pinfunction "2_2") (pintype "passive"))
      (node (ref "IC2") (pin "5") (pinfunction "CPL_F_5") (pintype "output"))
    )
    (net (code "22") (name "Net-(IC2-CPL_R)") (class "Default")
      (node (ref "C10") (pin "2") (pinfunction "2_2") (pintype "passive"))
      (node (ref "IC2") (pin "4") (pinfunction "CPL_R_4") (pintype "output"))
    )
    (net (code "23") (name "Net-(IC2-OUT)") (class "Default")
      (node (ref "C12") (pin "2") (pinfunction "2_2") (pintype "passive"))
      (node (ref "IC2") (pin "1") (pinfunction "OUT_1") (pintype "output"))
    )
    (net (code "24") (name "Net-(IC3-CRMS)") (class "Default")
      (node (ref "C19") (pin "1") (pinfunction "1_1") (pintype "passive"))
      (node (ref "IC3") (pin "9") (pinfunction "CRMS_9") (pintype "input"))
    )
    (net (code "25") (name "Net-(IC3-DECL)") (class "Default")
      (node (ref "C19") (pin "2") (pinfunction "2_2") (pintype "passive"))
      (node (ref "IC3") (pin "4") (pinfunction "DECL_4") (pintype "input"))
      (node (ref "R26") (pin "1") (pinfunction "1_1") (pintype "passive"))
    )
    (net (code "26") (name "Net-(IC3-ENBL)") (class "Default")
      (node (ref "IC3") (pin "14") (pinfunction "ENBL_14") (pintype "input"))
      (node (ref "R18") (pin "2") (pinfunction "2_2") (pintype "passive"))
    )
    (net (code "27") (name "Net-(IC3-Q)") (class "Default")
      (node (ref "IC3") (pin "12") (pinfunction "Q_12") (pintype "output"))
      (node (ref "R25") (pin "2") (pinfunction "2_2") (pintype "passive"))
    )
    (net (code "28") (name "Net-(IC3-RFIN)") (class "Default")
      (node (ref "C15") (pin "1") (pinfunction "1_1") (pintype "passive"))
      (node (ref "IC3") (pin "1") (pinfunction "RFIN_1") (pintype "input"))
    )
    (net (code "29") (name "Net-(IC3-RST)") (class "Default")
      (node (ref "IC3") (pin "15") (pinfunction "RST_15") (pintype "input"))
      (node (ref "R21") (pin "2") (pinfunction "2_2") (pintype "passive"))
      (node (ref "R7") (pin "1") (pinfunction "1_1") (pintype "passive"))
    )
    (net (code "30") (name "Net-(IC3-VIN-)") (class "Default")
      (node (ref "C30") (pin "2") (pinfunction "2_2") (pintype "passive"))
      (node (ref "IC3") (pin "16") (pinfunction "VIN-_16") (pintype "input"))
      (node (ref "R20") (pin "2") (pinfunction "2_2") (pintype "passive"))
      (node (ref "R40") (pin "1") (pinfunction "1_1") (pintype "passive"))
    )
    (net (code "31") (name "Net-(IC3-VRMS)") (class "Default")
      (node (ref "IC3") (pin "10") (pinfunction "VRMS_10") (pintype "output"))
      (node (ref "R29") (pin "2") (pinfunction "2_2") (pintype "passive"))
    )
    (net (code "32") (name "Net-(IC3-~{Q})") (class "Default")
      (node (ref "IC3") (pin "13") (pinfunction "~{Q}_13") (pintype "output"))
      (node (ref "R38") (pin "2") (pinfunction "2_2") (pintype "passive"))
    )
    (net (code "33") (name "Net-(IC4-CRMS)") (class "Default")
      (node (ref "C22") (pin "1") (pinfunction "1_1") (pintype "passive"))
      (node (ref "IC4") (pin "9") (pinfunction "CRMS_9") (pintype "input"))
    )
    (net (code "34") (name "Net-(IC4-DECL)") (class "Default")
      (node (ref "C22") (pin "2") (pinfunction "2_2") (pintype "passive"))
      (node (ref "IC4") (pin "4") (pinfunction "DECL_4") (pintype "input"))
      (node (ref "R27") (pin "1") (pinfunction "1_1") (pintype "passive"))
    )
    (net (code "35") (name "Net-(IC4-ENBL)") (class "Default")
      (node (ref "IC4") (pin "14") (pinfunction "ENBL_14") (pintype "input"))
      (node (ref "R19") (pin "1") (pinfunction "1_1") (pintype "passive"))
    )
    (net (code "36") (name "Net-(IC4-Q)") (class "Default")
      (node (ref "IC4") (pin "12") (pinfunction "Q_12") (pintype "output"))
      (node (ref "R37") (pin "2") (pinfunction "2_2") (pintype "passive"))
    )
    (net (code "37") (name "Net-(IC4-RFIN)") (class "Default")
      (node (ref "C16") (pin "1") (pinfunction "1_1") (pintype "passive"))
      (node (ref "IC4") (pin "1") (pinfunction "RFIN_1") (pintype "input"))
    )
    (net (code "38") (name "Net-(IC4-RST)") (class "Default")
      (node (ref "IC4") (pin "15") (pinfunction "RST_15") (pintype "input"))
      (node (ref "R2") (pin "1") (pinfunction "1_1") (pintype "passive"))
      (node (ref "R9") (pin "2") (pinfunction "2_2") (pintype "passive"))
    )
    (net (code "39") (name "Net-(IC4-VIN-)") (class "Default")
      (node (ref "C25") (pin "2") (pinfunction "2_2") (pintype "passive"))
      (node (ref "IC4") (pin "16") (pinfunction "VIN-_16") (pintype "input"))
      (node (ref "R24") (pin "2") (pinfunction "2_2") (pintype "passive"))
      (node (ref "R28") (pin "1") (pinfunction "1_1") (pintype "passive"))
    )
    (net (code "40") (name "Net-(IC4-VRMS)") (class "Default")
      (node (ref "IC4") (pin "10") (pinfunction "VRMS_10") (pintype "output"))
      (node (ref "R30") (pin "2") (pinfunction "2_2") (pintype "passive"))
    )
    (net (code "41") (name "Net-(IC4-~{Q})") (class "Default")
      (node (ref "IC4") (pin "13") (pinfunction "~{Q}_13") (pintype "output"))
      (node (ref "R39") (pin "2") (pinfunction "2_2") (pintype "passive"))
    )
    (net (code "42") (name "Net-(IC5-IN+)") (class "Default")
      (node (ref "C26") (pin "2") (pinfunction "2_2") (pintype "passive"))
      (node (ref "IC5") (pin "3") (pinfunction "IN+_3") (pintype "input"))
      (node (ref "R29") (pin "1") (pinfunction "1_1") (pintype "passive"))
    )
    (net (code "43") (name "Net-(IC5-IN-)") (class "Default")
      (node (ref "IC5") (pin "4") (pinfunction "IN-_4") (pintype "input"))
      (node (ref "R22") (pin "2") (pinfunction "2_2") (pintype "passive"))
      (node (ref "R31") (pin "2") (pinfunction "2_2") (pintype "passive"))
    )
    (net (code "44") (name "Net-(IC5-OUT)") (class "Default")
      (node (ref "IC5") (pin "1") (pinfunction "OUT_1") (pintype "output"))
      (node (ref "R22") (pin "1") (pinfunction "1_1") (pintype "passive"))
      (node (ref "R41") (pin "2") (pinfunction "2_2") (pintype "passive"))
      (node (ref "R42") (pin "2") (pinfunction "2_2") (pintype "passive"))
    )
    (net (code "45") (name "Net-(IC5-V+)") (class "Default")
      (node (ref "C21") (pin "2") (pinfunction "2_2") (pintype "passive"))
      (node (ref "IC5") (pin "5") (pinfunction "V+_5") (pintype "power_in"))
      (node (ref "L1") (pin "1") (pinfunction "1_1") (pintype "passive"))
    )
    (net (code "46") (name "Net-(IC6-IN+)") (class "Default")
      (node (ref "C27") (pin "2") (pinfunction "2_2") (pintype "passive"))
      (node (ref "IC6") (pin "3") (pinfunction "IN+_3") (pintype "input"))
      (node (ref "R30") (pin "1") (pinfunction "1_1") (pintype "passive"))
    )
    (net (code "47") (name "Net-(IC6-IN-)") (class "Default")
      (node (ref "IC6") (pin "4") (pinfunction "IN-_4") (pintype "input"))
      (node (ref "R23") (pin "2") (pinfunction "2_2") (pintype "passive"))
      (node (ref "R32") (pin "2") (pinfunction "2_2") (pintype "passive"))
    )
    (net (code "48") (name "Net-(IC6-OUT)") (class "Default")
      (node (ref "IC6") (pin "1") (pinfunction "OUT_1") (pintype "output"))
      (node (ref "R12") (pin "1") (pinfunction "1_1") (pintype "passive"))
      (node (ref "R17") (pin "1") (pinfunction "1_1") (pintype "passive"))
      (node (ref "R23") (pin "1") (pinfunction "1_1") (pintype "passive"))
    )
    (net (code "49") (name "Net-(IC6-V+)") (class "Default")
      (node (ref "C24") (pin "2") (pinfunction "2_2") (pintype "passive"))
      (node (ref "IC6") (pin "5") (pinfunction "V+_5") (pintype "power_in"))
      (node (ref "L4") (pin "1") (pinfunction "1_1") (pintype "passive"))
    )
    (net (code "50") (name "Net-(IC7-DXP)") (class "Default")
      (node (ref "C35") (pin "2") (pinfunction "2_2") (pintype "passive"))
      (node (ref "IC7") (pin "3") (pinfunction "DXP_3") (pintype "input"))
      (node (ref "T2") (pin "2") (pinfunction "E_2") (pintype "passive"))
    )
    (net (code "51") (name "Net-(IC7-VCC)") (class "Default")
      (node (ref "C29") (pin "2") (pinfunction "2_2") (pintype "passive"))
      (node (ref "IC7") (pin "1") (pinfunction "VCC_1") (pintype "power_in"))
      (node (ref "R33") (pin "1") (pinfunction "1_1") (pintype "passive"))
    )
    (net (code "52") (name "Net-(IC8-IN-)") (class "Default")
      (node (ref "IC8") (pin "4") (pinfunction "IN-_4") (pintype "input"))
      (node (ref "R4") (pin "1") (pinfunction "1_1") (pintype "passive"))
      (node (ref "R51") (pin "2") (pinfunction "2_2") (pintype "passive"))
    )
    (net (code "53") (name "Net-(IC8-OUT)") (class "Default")
      (node (ref "IC8") (pin "1") (pinfunction "OUT_1") (pintype "output"))
      (node (ref "R4") (pin "2") (pinfunction "2_2") (pintype "passive"))
      (node (ref "R5") (pin "2") (pinfunction "2_2") (pintype "passive"))
    )
    (net (code "54") (name "OUT_BIAS") (class "Default")
      (node (ref "P6") (pin "8") (pinfunction "8_8") (pintype "passive"))
      (node (ref "R51") (pin "1") (pinfunction "1_1") (pintype "passive"))
    )
    (net (code "55") (name "P3V3") (class "Default")
      (node (ref "C13") (pin "2") (pinfunction "2_2") (pintype "passive"))
      (node (ref "P6") (pin "6") (pinfunction "6_6") (pintype "passive"))
      (node (ref "R33") (pin "2") (pinfunction "2_2") (pintype "passive"))
      (node (ref "R34") (pin "1") (pinfunction "1_1") (pintype "passive"))
      (node (ref "R35") (pin "1") (pinfunction "1_1") (pintype "passive"))
      (node (ref "R36") (pin "1") (pinfunction "1_1") (pintype "passive"))
    )
    (net (code "56") (name "P3V3A1") (class "Default")
      (node (ref "C14") (pin "2") (pinfunction "2_2") (pintype "passive"))
      (node (ref "C17") (pin "2") (pinfunction "2_2") (pintype "passive"))
      (node (ref "C8") (pin "2") (pinfunction "2_2") (pintype "passive"))
      (node (ref "IC3") (pin "5") (pinfunction "VPOS_5") (pintype "power_in"))
      (node (ref "IC3") (pin "7") (pinfunction "VPOS_7") (pintype "power_in"))
      (node (ref "IC4") (pin "5") (pinfunction "VPOS_5") (pintype "power_in"))
      (node (ref "IC4") (pin "7") (pinfunction "VPOS_7") (pintype "power_in"))
      (node (ref "IC8") (pin "5") (pinfunction "V+_5") (pintype "power_in"))
      (node (ref "L1") (pin "2") (pinfunction "2_2") (pintype "passive"))
      (node (ref "L4") (pin "2") (pinfunction "2_2") (pintype "passive"))
      (node (ref "P3") (pin "8") (pinfunction "8_8") (pintype "passive"))
      (node (ref "R18") (pin "1") (pinfunction "1_1") (pintype "passive"))
      (node (ref "R19") (pin "2") (pinfunction "2_2") (pintype "passive"))
    )
    (net (code "57") (name "VCC_PWRAMP") (class "Default")
      (node (ref "C5") (pin "2") (pinfunction "2_2") (pintype "passive"))
      (node (ref "C6") (pin "2") (pinfunction "2_2") (pintype "passive"))
      (node (ref "C7") (pin "2") (pinfunction "2_2") (pintype "passive"))
      (node (ref "IC1") (pin "5") (pinfunction "VCC_5") (pintype "power_in"))
      (node (ref "P6") (pin "2") (pinfunction "2_2") (pintype "passive"))
      (node (ref "P6") (pin "4") (pinfunction "4_4") (pintype "passive"))
    )
    (net (code "58") (name "unconnected-(IC3-DNC-Pad2)") (class "Default")
      (node (ref "IC3") (pin "2") (pinfunction "DNC_2") (pintype "passive+no_connect"))
    )
    (net (code "59") (name "unconnected-(IC3-DNC-Pad6)") (class "Default")
      (node (ref "IC3") (pin "6") (pinfunction "DNC_6") (pintype "passive+no_connect"))
    )
    (net (code "60") (name "unconnected-(IC3-DNC-Pad8)") (class "Default")
      (node (ref "IC3") (pin "8") (pinfunction "DNC_8") (pintype "passive+no_connect"))
    )
    (net (code "61") (name "unconnected-(IC3-VCAL-Pad3)") (class "Default")
      (node (ref "IC3") (pin "3") (pinfunction "VCAL_3") (pintype "input+no_connect"))
    )
    (net (code "62") (name "unconnected-(IC4-DNC-Pad2)") (class "Default")
      (node (ref "IC4") (pin "2") (pinfunction "DNC_2") (pintype "passive+no_connect"))
    )
    (net (code "63") (name "unconnected-(IC4-DNC-Pad6)") (class "Default")
      (node (ref "IC4") (pin "6") (pinfunction "DNC_6") (pintype "passive+no_connect"))
    )
    (net (code "64") (name "unconnected-(IC4-DNC-Pad8)") (class "Default")
      (node (ref "IC4") (pin "8") (pinfunction "DNC_8") (pintype "passive+no_connect"))
    )
    (net (code "65") (name "unconnected-(IC4-VCAL-Pad3)") (class "Default")
      (node (ref "IC4") (pin "3") (pinfunction "VCAL_3") (pintype "input+no_connect"))
    )
  )
)
